# RFD_PWR_MGMT.net
KiCad netlist of a schematic drawn in Altium Designer
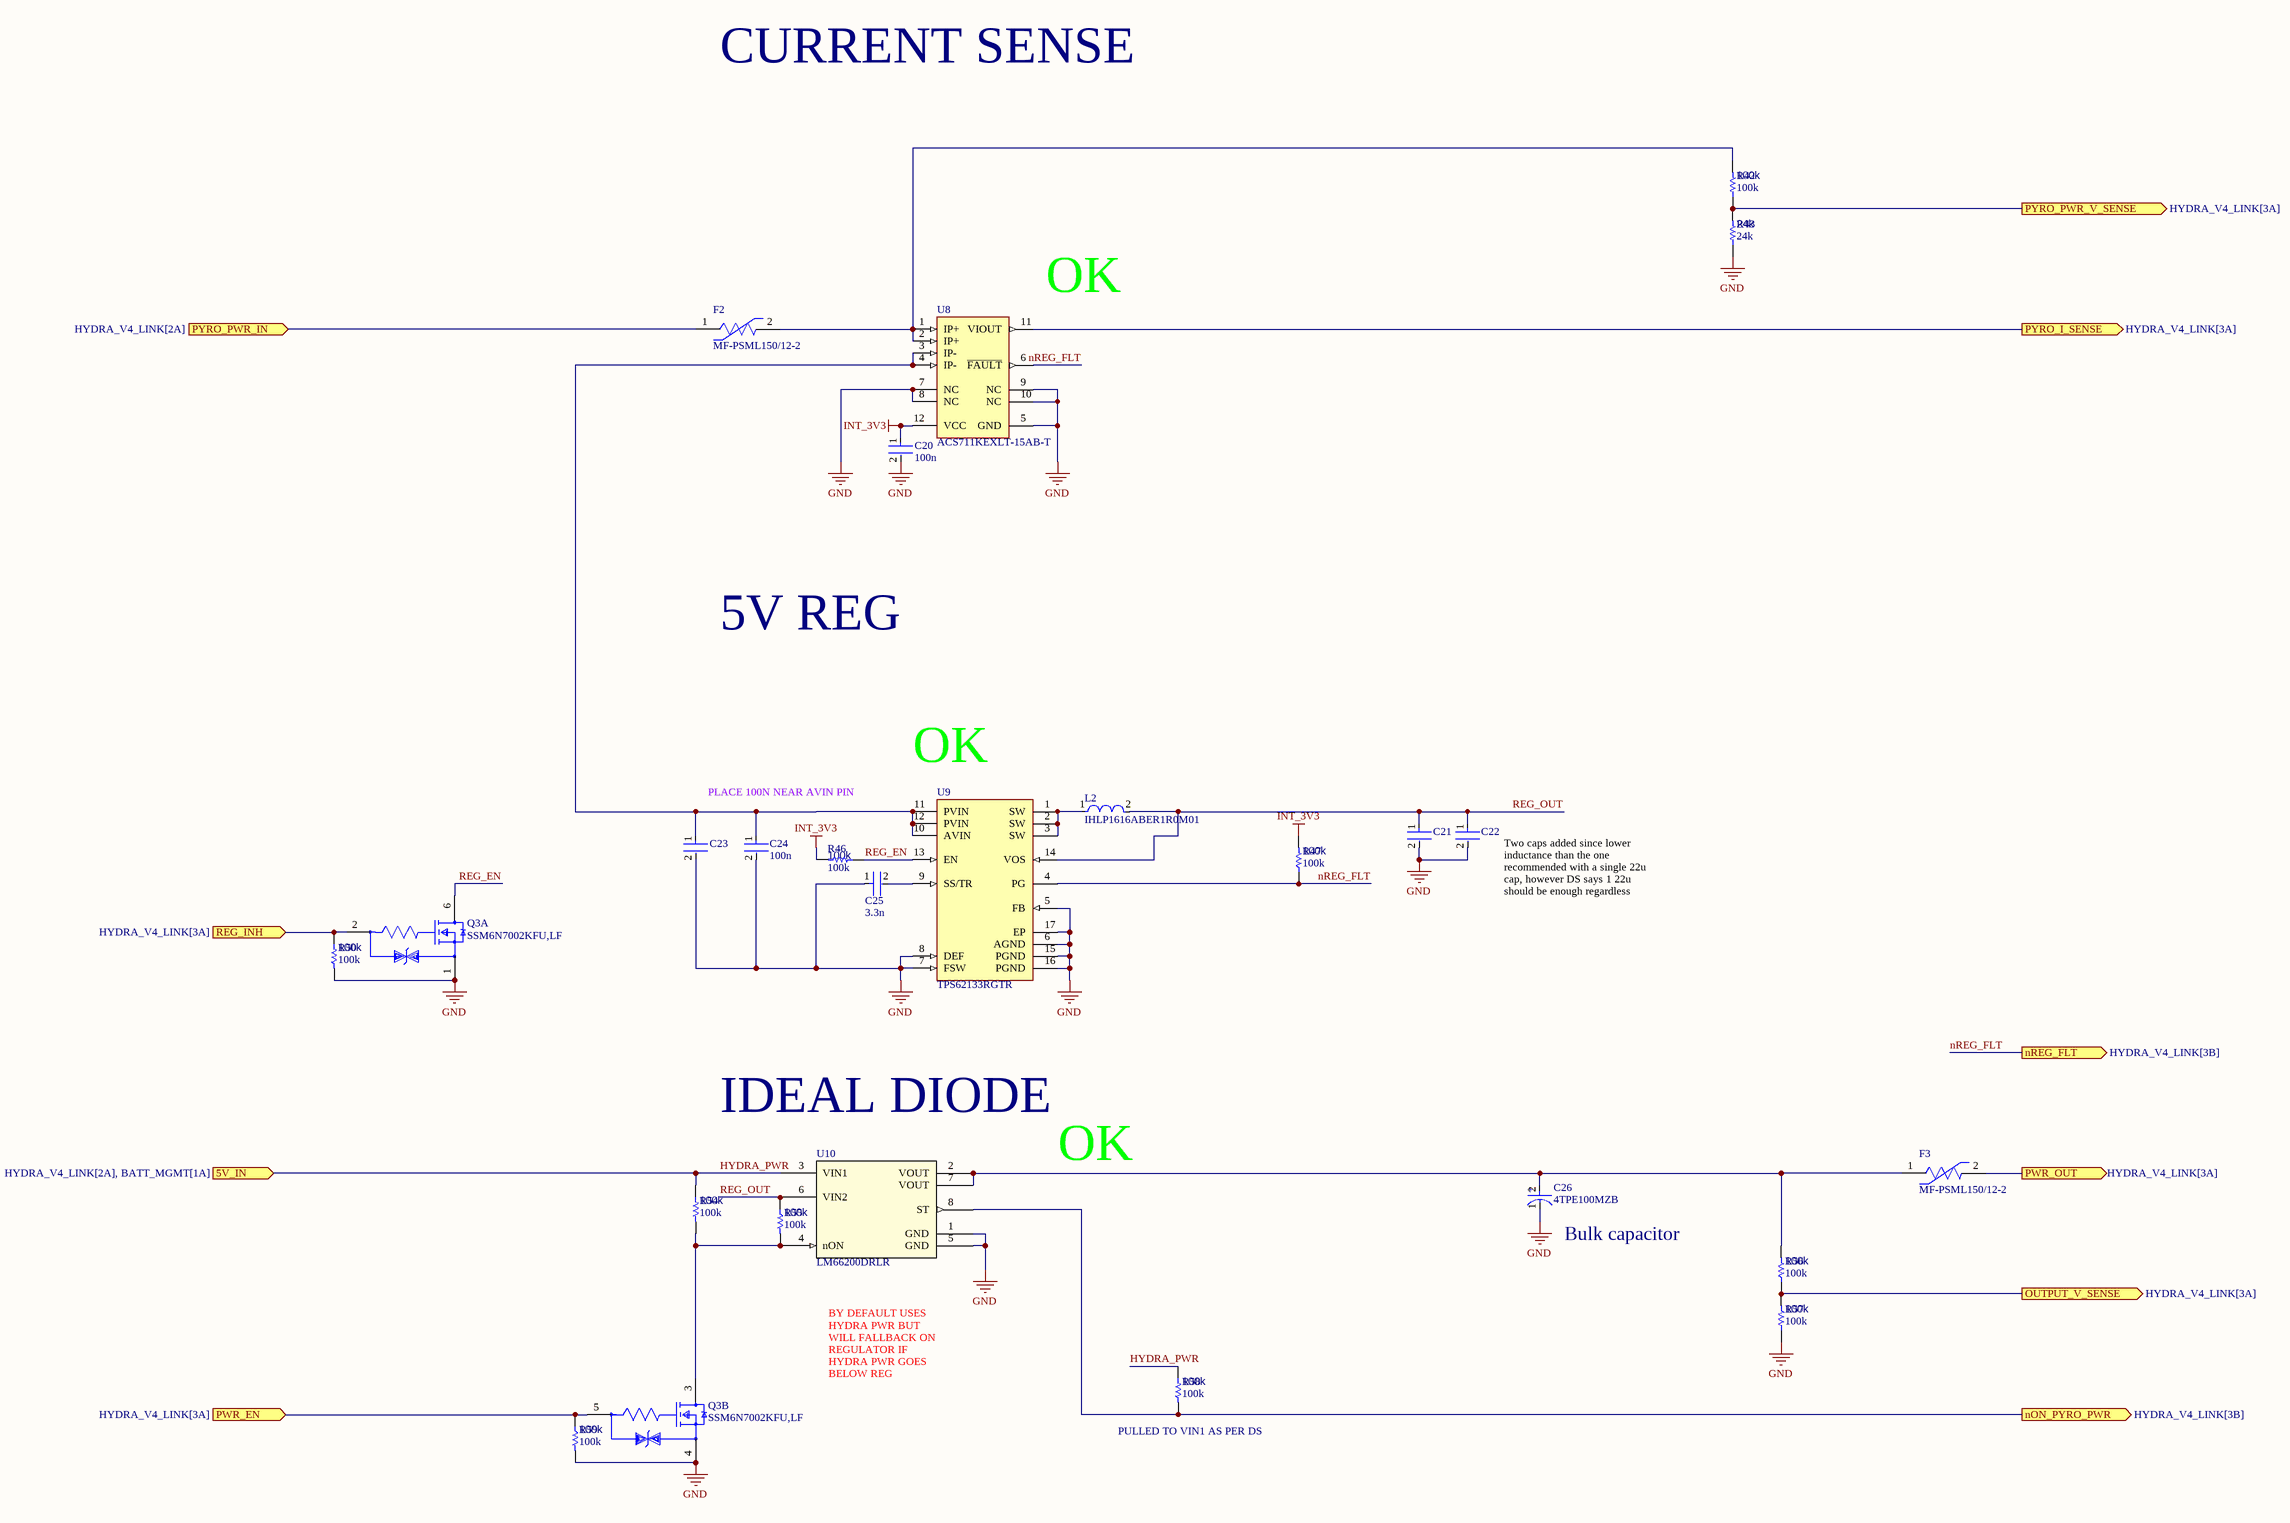
[diagram p0: RFD_PWR_MGMT.SchDoc]

(export (version "E")
  (design (tool "Eeschema 10.0.6"))
  (components
    (comp (ref "C20")
      (value "100n")
      (footprint "FP-0402-L_1_0_0_05-W_0_5-IPC_A")
      (description "LARGE PADS, 0402 CAP, CHANGE COMMENT TO MATCH REAL P/N")
      (libsource (lib "Space Concordia") (part "b4654b650e69147ec39a6b967a45e02"))
    )
    (comp (ref "C21")
      (value "GRM21BR61E226ME44L")
      (footprint "FP-GRM21B-0_2-e0_2_0_7-IPC_B")
      (description "Chip Multilayer Ceramic Capacitors for General Purpose, 0805, 22uF, X5R, 15%, 20%, 25V")
      (fields (field (name "TOLERANCE") "20%") (field (name "VOLTAGE") "25V"))
      (libsource (lib "Altium Content Vault") (part "b4654b650e69147ec39a6b967a45e02"))
    )
    (comp (ref "C22")
      (value "GRM21BR61E226ME44L")
      (footprint "FP-GRM21B-0_2-e0_2_0_7-IPC_B")
      (description "Chip Multilayer Ceramic Capacitors for General Purpose, 0805, 22uF, X5R, 15%, 20%, 25V")
      (fields (field (name "TOLERANCE") "20%") (field (name "VOLTAGE") "25V"))
      (libsource (lib "Altium Content Vault") (part "b4654b650e69147ec39a6b967a45e02"))
    )
    (comp (ref "C23")
      (value "TMK212BBJ106KG-T")
      (footprint "FP-0805-L_2_0_0_2-W_1_25-MFG")
      (description "Multilayer Ceramic Capacitor 10uF 25V X5R 10% SMD 0805 T/R")
      (fields (field (name "VOLTAGE") "16V") (field (name "TOLERANCE") "10%"))
      (libsource (lib "Altium Content Vault") (part "02cd4be3c70576c341d710602a673aa"))
    )
    (comp (ref "C24")
      (value "100n")
      (footprint "FP-0402-L_1_0_0_05-W_0_5-IPC_A")
      (description "LARGE PADS, 0402 CAP, CHANGE COMMENT TO MATCH REAL P/N")
      (libsource (lib "Space Concordia") (part "b4654b650e69147ec39a6b967a45e02"))
    )
    (comp (ref "C25")
      (value "3.3n")
      (footprint "FP-0402-L_1_0_0_05-W_0_5-IPC_A")
      (description "LARGE PADS, 0402 CAP, CHANGE COMMENT TO MATCH REAL P/N")
      (libsource (lib "Space Concordia") (part "b4654b650e69147ec39a6b967a45e02"))
    )
    (comp (ref "C26")
      (value "4TPE100MZB")
      (footprint "FP-POSCAP-B2-MFG")
      (description "Molded Tantalum Polymer Capacitor 100uF 20% 4V life 1000Hours SMD 1411")
      (fields (field (name "VOLTAGE") "4V") (field (name "TOLERANCE") "20%"))
      (libsource (lib "Altium Content Vault") (part "cf48714ba7e38822c1575c7ec0b6d1f"))
    )
    (comp (ref "F2")
      (value "MF-PSML150/12-2")
      (footprint "FP-MF-PSMF-MFG")
      (fields
        (field (name "MANUFACTURER PART NUMBER") "MF-PSMF050X-2")
        (field (name "MANUFACTURER") "Bourns Inc.")
        (field (name "OCTOPART") "https://octopart.com/mf-psmf050x-2-bourns-7483438")
      )
      (libsource (lib "Altium Content Vault") (part "fdf083d5f6389a9a1c4e51137f46658"))
    )
    (comp (ref "F3")
      (value "MF-PSML150/12-2")
      (footprint "FP-MF-PSMF-MFG")
      (fields
        (field (name "MANUFACTURER PART NUMBER") "MF-PSMF050X-2")
        (field (name "MANUFACTURER") "Bourns Inc.")
        (field (name "OCTOPART") "https://octopart.com/mf-psmf050x-2-bourns-7483438")
      )
      (libsource (lib "Altium Content Vault") (part "fdf083d5f6389a9a1c4e51137f46658"))
    )
    (comp (ref "L2")
      (value "IHLP1616ABER1R0M01")
      (footprint "FP-IHLP-1616AB-FP_1_8545x-MFG")
      (description "Fixed Inductors Commercial High Saturation Series SMT 1uH 4A 52.5mΩ 20%")
      (fields (field (name "TOLERANCE") "20%"))
      (libsource (lib "Altium Content Vault") (part "725321dda6339637d4d059423bc1c3c"))
    )
    (comp (ref "Q3")
      (value "SSM6N7002KFU,LF")
      (footprint "FP-SSOP6-P-0_65A-MFG")
      (description "Transistor MOSFET Array Dual N-CH 60V 300mA 6-Pin SOT-363 Emboss T/R")
      (libsource (lib "Space Concordia") (part "088aa6ac103fdeebe0d1c52ece6b7b9"))
    )
    (comp (ref "R42")
      (value "100k")
      (footprint "R0603B")
      (description "Resistor")
      (fields (field (name "ALTIUM_VALUE") "100k"))
      (libsource (lib "Space Concordia") (part "Resistor"))
    )
    (comp (ref "R43")
      (value "24k")
      (footprint "R0603B")
      (description "Resistor")
      (fields (field (name "ALTIUM_VALUE") "24k"))
      (libsource (lib "Space Concordia") (part "Resistor"))
    )
    (comp (ref "R46")
      (value "100k")
      (footprint "R0603B")
      (description "Resistor")
      (fields (field (name "ALTIUM_VALUE") "100k"))
      (libsource (lib "Space Concordia") (part "Resistor"))
    )
    (comp (ref "R47")
      (value "100k")
      (footprint "R0603B")
      (description "Resistor")
      (fields (field (name "ALTIUM_VALUE") "100k"))
      (libsource (lib "Space Concordia") (part "Resistor"))
    )
    (comp (ref "R50")
      (value "100k")
      (footprint "R0603B")
      (description "Resistor")
      (fields (field (name "ALTIUM_VALUE") "100k"))
      (libsource (lib "Space Concordia") (part "Resistor"))
    )
    (comp (ref "R54")
      (value "100k")
      (footprint "R0603B")
      (description "Resistor")
      (fields (field (name "ALTIUM_VALUE") "100k"))
      (libsource (lib "Space Concordia") (part "Resistor"))
    )
    (comp (ref "R55")
      (value "100k")
      (footprint "R0603B")
      (description "Resistor")
      (fields (field (name "ALTIUM_VALUE") "100k"))
      (libsource (lib "Space Concordia") (part "Resistor"))
    )
    (comp (ref "R56")
      (value "100k")
      (footprint "R0603B")
      (description "Resistor")
      (fields (field (name "ALTIUM_VALUE") "100k"))
      (libsource (lib "Space Concordia") (part "Resistor"))
    )
    (comp (ref "R57")
      (value "100k")
      (footprint "R0603B")
      (description "Resistor")
      (fields (field (name "ALTIUM_VALUE") "100k"))
      (libsource (lib "Space Concordia") (part "Resistor"))
    )
    (comp (ref "R58")
      (value "100k")
      (footprint "R0603B")
      (description "Resistor")
      (fields (field (name "ALTIUM_VALUE") "100k"))
      (libsource (lib "Space Concordia") (part "Resistor"))
    )
    (comp (ref "R59")
      (value "100k")
      (footprint "R0603B")
      (description "Resistor")
      (fields (field (name "ALTIUM_VALUE") "100k"))
      (libsource (lib "Space Concordia") (part "Resistor"))
    )
    (comp (ref "U8")
      (value "ACS711KEXLT-15AB-T")
      (footprint "ALEG-EX-12_V")
      (libsource (lib "Altium Content Vault") (part "ALEG-ACS711-QFN-12"))
    )
    (comp (ref "U9")
      (value "TPS62133RGTR")
      (footprint "RGT0016C_V")
      (fields (field (name "MANUFACTURER") "Texas Instruments"))
      (libsource (lib "Altium Content Vault") (part "TI-TPS62133RGT16-1700X1700TP"))
    )
    (comp (ref "U10")
      (value "LM66200DRLR")
      (footprint "LM66200DRLR-Footprint-1")
      (description "1.6-V to 5.5-V, 40-mΩ, 2.5-A, low-IQ, dual ideal diode 8-SOT-5X3 -40 to 125")
      (libsource (lib "Space Concordia") (part "LM66200DRLR"))
    )
  )
  (nets
    (net (code "1") (name "/HYDRA_PWR") (class "Default")
      (node (ref "R54") (pin "1") (pinfunction "1_1") (pintype "passive"))
      (node (ref "R58") (pin "1") (pinfunction "1_1") (pintype "passive"))
      (node (ref "U10") (pin "3") (pinfunction "VIN1_3") (pintype "power_in"))
    )
    (net (code "2") (name "/OUTPUT_V_SENSE") (class "Default")
      (node (ref "R56") (pin "1") (pinfunction "1_1") (pintype "passive"))
      (node (ref "R57") (pin "2") (pinfunction "2_2") (pintype "passive"))
    )
    (net (code "3") (name "/PWR_EN") (class "Default")
      (node (ref "Q3") (pin "5") (pinfunction "Gate2_5") (pintype "passive"))
      (node (ref "R59") (pin "1") (pinfunction "1_1") (pintype "passive"))
    )
    (net (code "4") (name "/PWR_OUT") (class "Default")
      (node (ref "F3") (pin "2") (pinfunction "2_2") (pintype "passive"))
    )
    (net (code "5") (name "/PYRO_I_SENSE") (class "Default")
      (node (ref "U8") (pin "11") (pinfunction "VIOUT_11") (pintype "output"))
    )
    (net (code "6") (name "/PYRO_PWR_IN") (class "Default")
      (node (ref "F2") (pin "1") (pinfunction "1_1") (pintype "passive"))
    )
    (net (code "7") (name "/PYRO_PWR_V_SENSE") (class "Default")
      (node (ref "R42") (pin "1") (pinfunction "1_1") (pintype "passive"))
      (node (ref "R43") (pin "2") (pinfunction "2_2") (pintype "passive"))
    )
    (net (code "8") (name "/REG_EN") (class "Default")
      (node (ref "Q3") (pin "6") (pinfunction "Drain1_6") (pintype "passive"))
      (node (ref "R46") (pin "1") (pinfunction "1_1") (pintype "passive"))
      (node (ref "U9") (pin "13") (pinfunction "EN_13") (pintype "input"))
    )
    (net (code "9") (name "/REG_INH") (class "Default")
      (node (ref "Q3") (pin "2") (pinfunction "Gate1_2") (pintype "passive"))
      (node (ref "R50") (pin "1") (pinfunction "1_1") (pintype "passive"))
    )
    (net (code "10") (name "/REG_OUT") (class "Default")
      (node (ref "C21") (pin "1") (pinfunction "1_1") (pintype "passive"))
      (node (ref "C22") (pin "1") (pinfunction "1_1") (pintype "passive"))
      (node (ref "L2") (pin "2") (pinfunction "2_2") (pintype "passive"))
      (node (ref "R55") (pin "1") (pinfunction "1_1") (pintype "passive"))
      (node (ref "U10") (pin "6") (pinfunction "VIN2_6") (pintype "power_in"))
      (node (ref "U9") (pin "14") (pinfunction "VOS_14") (pintype "input"))
    )
    (net (code "11") (name "/nON_PYRO_PWR") (class "Default")
      (node (ref "R58") (pin "2") (pinfunction "2_2") (pintype "passive"))
      (node (ref "U10") (pin "8") (pinfunction "ST_8") (pintype "output"))
    )
    (net (code "12") (name "/nREG_FLT") (class "Default")
      (node (ref "R47") (pin "1") (pinfunction "1_1") (pintype "passive"))
      (node (ref "U8") (pin "6") (pinfunction "~{FAULT}_6") (pintype "output"))
      (node (ref "U9") (pin "4") (pinfunction "PG_4") (pintype "tri_state"))
    )
    (net (code "13") (name "GND") (class "Default")
      (node (ref "C20") (pin "2") (pinfunction "2_2") (pintype "passive"))
      (node (ref "C21") (pin "2") (pinfunction "2_2") (pintype "passive"))
      (node (ref "C22") (pin "2") (pinfunction "2_2") (pintype "passive"))
      (node (ref "C23") (pin "2") (pinfunction "2_2") (pintype "passive"))
      (node (ref "C24") (pin "2") (pinfunction "2_2") (pintype "passive"))
      (node (ref "C25") (pin "1") (pinfunction "1_1") (pintype "passive"))
      (node (ref "C26") (pin "1") (pinfunction "C_1") (pintype "passive"))
      (node (ref "Q3") (pin "1") (pinfunction "Source1_1") (pintype "passive"))
      (node (ref "Q3") (pin "4") (pinfunction "Source2_4") (pintype "passive"))
      (node (ref "R43") (pin "1") (pinfunction "1_1") (pintype "passive"))
      (node (ref "R50") (pin "2") (pinfunction "2_2") (pintype "passive"))
      (node (ref "R57") (pin "1") (pinfunction "1_1") (pintype "passive"))
      (node (ref "R59") (pin "2") (pinfunction "2_2") (pintype "passive"))
      (node (ref "U10") (pin "1") (pinfunction "GND_1") (pintype "power_in"))
      (node (ref "U10") (pin "5") (pinfunction "GND_5") (pintype "power_in"))
      (node (ref "U8") (pin "10") (pinfunction "NC_10") (pintype "passive"))
      (node (ref "U8") (pin "5") (pinfunction "GND_5") (pintype "power_in"))
      (node (ref "U8") (pin "7") (pinfunction "NC_7") (pintype "passive"))
      (node (ref "U8") (pin "8") (pinfunction "NC_8") (pintype "passive"))
      (node (ref "U8") (pin "9") (pinfunction "NC_9") (pintype "passive"))
      (node (ref "U9") (pin "15") (pinfunction "PGND_15") (pintype "power_in"))
      (node (ref "U9") (pin "16") (pinfunction "PGND_16") (pintype "power_in"))
      (node (ref "U9") (pin "17") (pinfunction "EP_17") (pintype "power_in"))
      (node (ref "U9") (pin "5") (pinfunction "FB_5") (pintype "input"))
      (node (ref "U9") (pin "6") (pinfunction "AGND_6") (pintype "power_in"))
      (node (ref "U9") (pin "7") (pinfunction "FSW_7") (pintype "input"))
      (node (ref "U9") (pin "8") (pinfunction "DEF_8") (pintype "input"))
    )
    (net (code "14") (name "INT_3V3") (class "Default")
      (node (ref "C20") (pin "1") (pinfunction "1_1") (pintype "passive"))
      (node (ref "R46") (pin "2") (pinfunction "2_2") (pintype "passive"))
      (node (ref "R47") (pin "2") (pinfunction "2_2") (pintype "passive"))
      (node (ref "U8") (pin "12") (pinfunction "VCC_12") (pintype "power_in"))
    )
    (net (code "15") (name "Net-(C26-A)") (class "Default")
      (node (ref "C26") (pin "2") (pinfunction "A_2") (pintype "passive"))
      (node (ref "F3") (pin "1") (pinfunction "1_1") (pintype "passive"))
      (node (ref "R56") (pin "2") (pinfunction "2_2") (pintype "passive"))
      (node (ref "U10") (pin "2") (pinfunction "VOUT_2") (pintype "power_in"))
      (node (ref "U10") (pin "7") (pinfunction "VOUT_7") (pintype "power_in"))
    )
    (net (code "16") (name "Net-(F2-Pad2)") (class "Default")
      (node (ref "F2") (pin "2") (pinfunction "2_2") (pintype "passive"))
      (node (ref "R42") (pin "2") (pinfunction "2_2") (pintype "passive"))
      (node (ref "U8") (pin "1") (pinfunction "IP+_1") (pintype "input"))
      (node (ref "U8") (pin "2") (pinfunction "IP+_2") (pintype "input"))
    )
    (net (code "17") (name "Net-(L2-Pad1)") (class "Default")
      (node (ref "L2") (pin "1") (pinfunction "1_1") (pintype "passive"))
      (node (ref "U9") (pin "1") (pinfunction "SW_1") (pintype "power_in"))
      (node (ref "U9") (pin "2") (pinfunction "SW_2") (pintype "power_in"))
      (node (ref "U9") (pin "3") (pinfunction "SW_3") (pintype "power_in"))
    )
    (net (code "18") (name "Net-(Q3B-Drain2)") (class "Default")
      (node (ref "Q3") (pin "3") (pinfunction "Drain2_3") (pintype "passive"))
      (node (ref "R54") (pin "2") (pinfunction "2_2") (pintype "passive"))
      (node (ref "R55") (pin "2") (pinfunction "2_2") (pintype "passive"))
      (node (ref "U10") (pin "4") (pinfunction "nON_4") (pintype "input"))
    )
    (net (code "19") (name "Net-(U9-AVIN)") (class "Default")
      (node (ref "C23") (pin "1") (pinfunction "1_1") (pintype "passive"))
      (node (ref "C24") (pin "1") (pinfunction "1_1") (pintype "passive"))
      (node (ref "U8") (pin "3") (pinfunction "IP-_3") (pintype "input"))
      (node (ref "U8") (pin "4") (pinfunction "IP-_4") (pintype "input"))
      (node (ref "U9") (pin "10") (pinfunction "AVIN_10") (pintype "power_in"))
      (node (ref "U9") (pin "11") (pinfunction "PVIN_11") (pintype "power_in"))
      (node (ref "U9") (pin "12") (pinfunction "PVIN_12") (pintype "power_in"))
    )
    (net (code "20") (name "Net-(U9-SS{slash}TR)") (class "Default")
      (node (ref "C25") (pin "2") (pinfunction "2_2") (pintype "passive"))
      (node (ref "U9") (pin "9") (pinfunction "SS/TR_9") (pintype "input"))
    )
  )
)
